# SparkFun_GPS_ZED-F9K.net
KiCad netlist of a schematic drawn in EAGLE
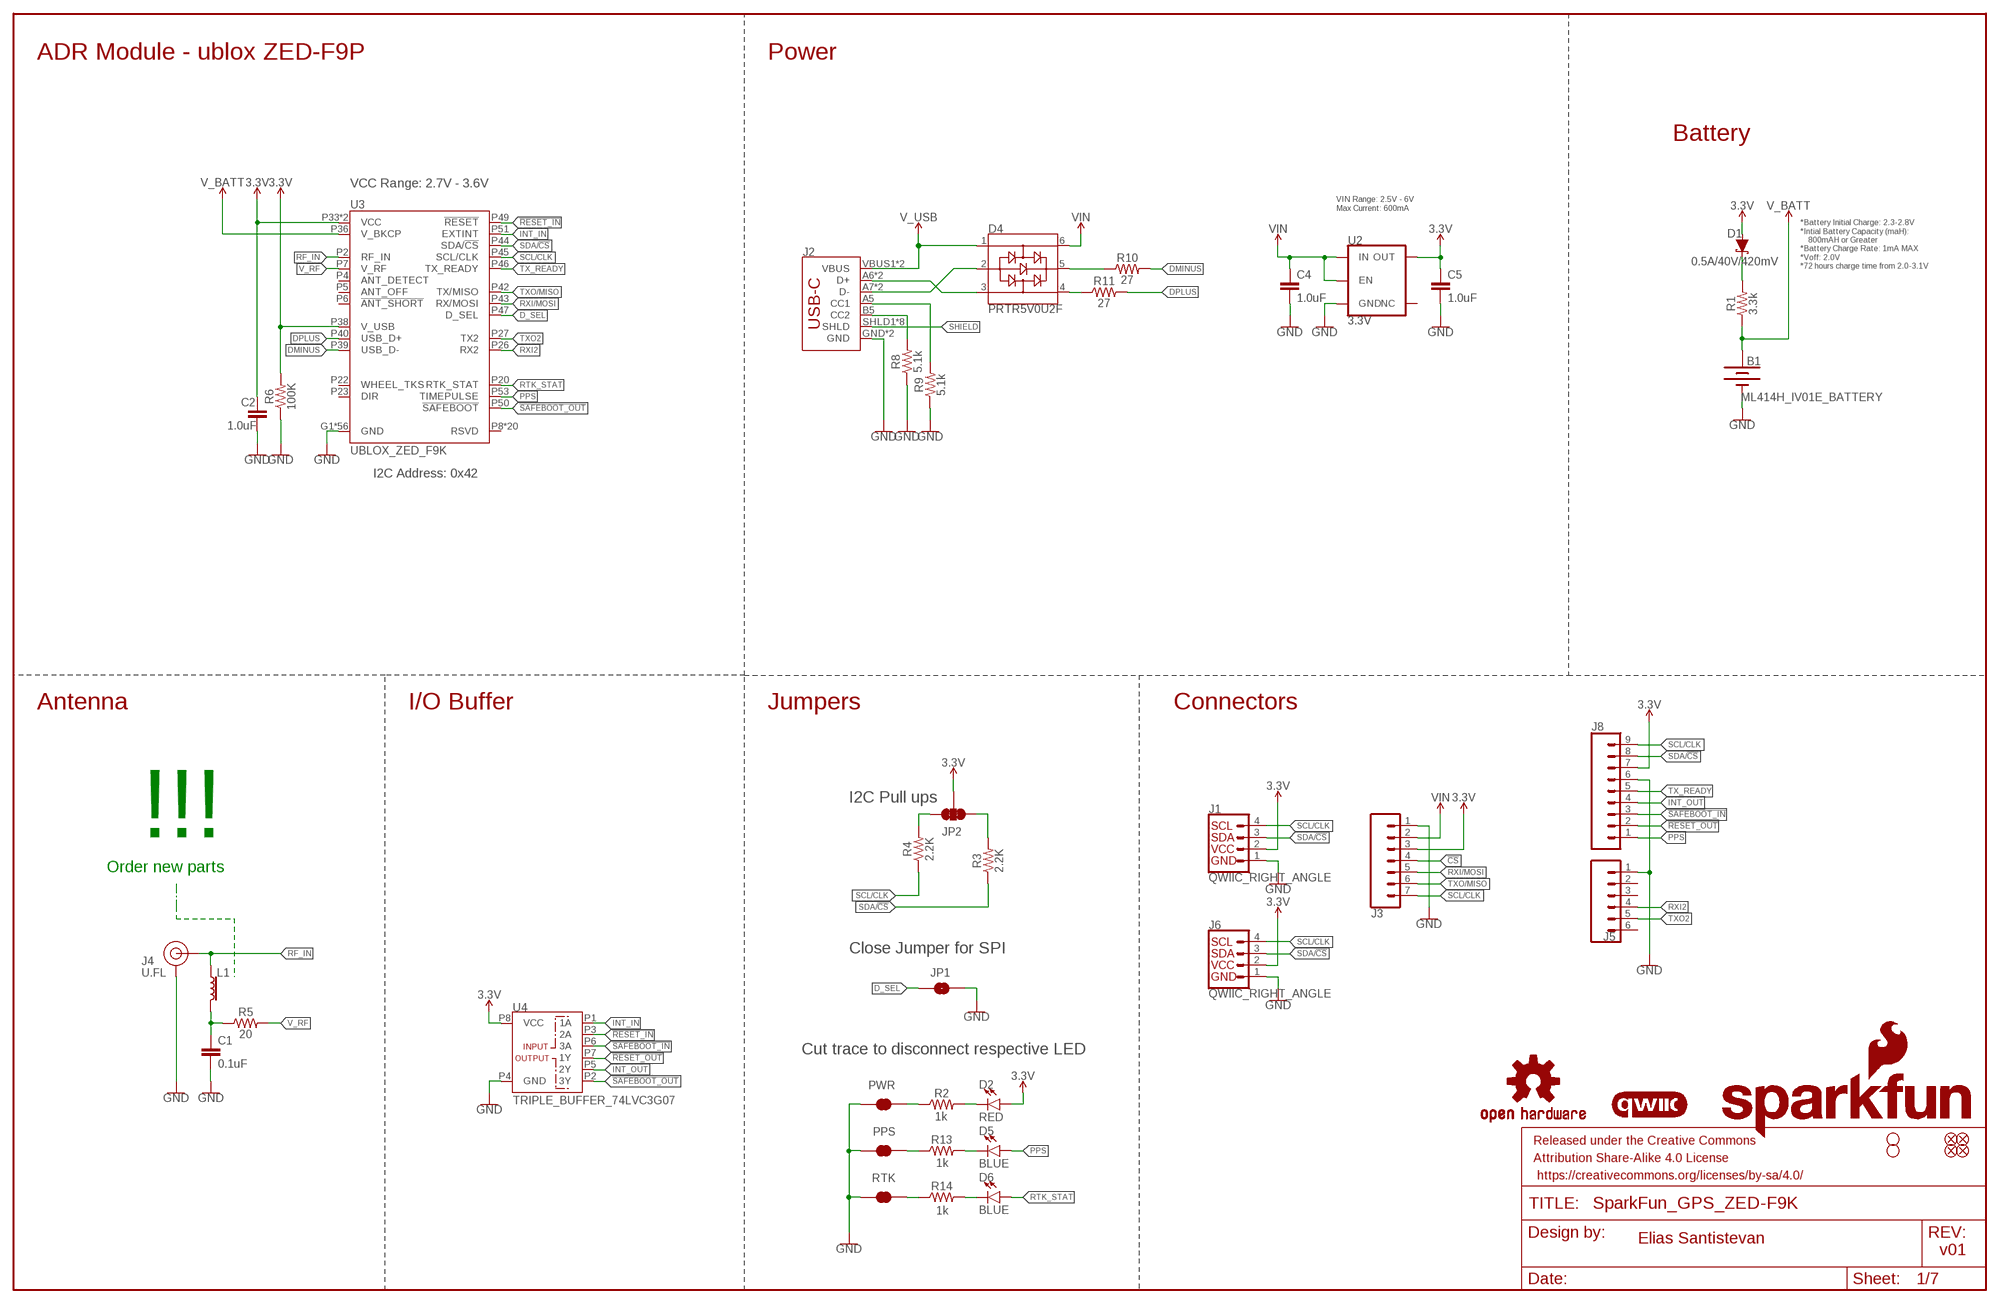
[diagram p0: schematic, sheet 1]

(export (version "E")
  (design (tool "Eeschema 10.0.6"))
  (components
    (comp (ref "B1")
      (value "ML414H_IV01E_BATTERY")
      (footprint "eagle-import:ML414H_IV01E")
      (libsource (lib "eagle-import") (part "ML414H_IV01E_BATTERY"))
    )
    (comp (ref "C1")
      (value "0.1uF")
      (footprint "eagle-import:0402")
      (libsource (lib "eagle-import") (part "0.1UF-0402-16V-10%"))
    )
    (comp (ref "C2")
      (value "1.0uF")
      (footprint "eagle-import:0402")
      (libsource (lib "eagle-import") (part "1.0UF-0402-16V-10%"))
    )
    (comp (ref "C4")
      (value "1.0uF")
      (footprint "eagle-import:0603")
      (libsource (lib "eagle-import") (part "1.0UF-0603-16V-10%-X7R"))
    )
    (comp (ref "C5")
      (value "1.0uF")
      (footprint "eagle-import:0603")
      (libsource (lib "eagle-import") (part "1.0UF-0603-16V-10%-X7R"))
    )
    (comp (ref "D1")
      (value "0.5A/40V/420mV")
      (footprint "eagle-import:SOD-323")
      (libsource (lib "eagle-import") (part "DIODE-SCHOTTKY-PMEG4005EJ"))
    )
    (comp (ref "D2")
      (value "RED")
      (footprint "eagle-import:LED-0603")
      (libsource (lib "eagle-import") (part "LED-RED0603"))
    )
    (comp (ref "D4")
      (value "PRTR5V0U2F")
      (footprint "eagle-import:SOT886")
      (libsource (lib "eagle-import") (part "PRTR5V0U2F"))
    )
    (comp (ref "D5")
      (value "BLUE")
      (footprint "eagle-import:LED-0603")
      (libsource (lib "eagle-import") (part "LED-BLUE0603"))
    )
    (comp (ref "D6")
      (value "BLUE")
      (footprint "eagle-import:LED-0603")
      (libsource (lib "eagle-import") (part "LED-BLUE0603"))
    )
    (comp (ref "FD1")
      (value "FIDUCIALUFIDUCIAL")
      (footprint "eagle-import:FIDUCIAL-MICRO")
      (libsource (lib "eagle-import") (part "FIDUCIALUFIDUCIAL"))
    )
    (comp (ref "FD2")
      (value "FIDUCIALUFIDUCIAL")
      (footprint "eagle-import:FIDUCIAL-MICRO")
      (libsource (lib "eagle-import") (part "FIDUCIALUFIDUCIAL"))
    )
    (comp (ref "FD3")
      (value "FIDUCIALUFIDUCIAL")
      (footprint "eagle-import:FIDUCIAL-MICRO")
      (libsource (lib "eagle-import") (part "FIDUCIALUFIDUCIAL"))
    )
    (comp (ref "FD4")
      (value "FIDUCIALUFIDUCIAL")
      (footprint "eagle-import:FIDUCIAL-MICRO")
      (libsource (lib "eagle-import") (part "FIDUCIALUFIDUCIAL"))
    )
    (comp (ref "FRAME2")
      (value "FRAME-LEDGER")
      (footprint "eagle-import:CREATIVE_COMMONS")
      (libsource (lib "eagle-import") (part "FRAME-LEDGER"))
    )
    (comp (ref "H2")
      (value "STAND-OFFTIGHT")
      (footprint "eagle-import:STAND-OFF-TIGHT")
      (libsource (lib "eagle-import") (part "STAND-OFFTIGHT"))
    )
    (comp (ref "H3")
      (value "STAND-OFFTIGHT")
      (footprint "eagle-import:STAND-OFF-TIGHT")
      (libsource (lib "eagle-import") (part "STAND-OFFTIGHT"))
    )
    (comp (ref "J1")
      (value "QWIIC_RIGHT_ANGLE")
      (footprint "eagle-import:JST04_1MM_RA")
      (libsource (lib "eagle-import") (part "QWIIC_CONNECTORJS-1MM"))
    )
    (comp (ref "J2")
      (value "USB_C2-LAYER")
      (footprint "eagle-import:USB-C-16P")
      (libsource (lib "eagle-import") (part "USB_C2-LAYER"))
    )
    (comp (ref "J3")
      (value "CONN_07NO_SILK")
      (footprint "eagle-import:1X07_NO_SILK")
      (libsource (lib "eagle-import") (part "CONN_07NO_SILK"))
    )
    (comp (ref "J4")
      (value "U.FL")
      (footprint "eagle-import:U.FL")
      (libsource (lib "eagle-import") (part "U.FL2PIN"))
    )
    (comp (ref "J5")
      (value "CONN_06NO_SILK_NO_POP")
      (footprint "eagle-import:1X06_NO_SILK")
      (libsource (lib "eagle-import") (part "CONN_06NO_SILK_NO_POP"))
    )
    (comp (ref "J6")
      (value "QWIIC_RIGHT_ANGLE")
      (footprint "eagle-import:JST04_1MM_RA")
      (libsource (lib "eagle-import") (part "QWIIC_CONNECTORJS-1MM"))
    )
    (comp (ref "J8")
      (value "CONN_09NO_SILK")
      (footprint "eagle-import:1X09_NO_SILK")
      (libsource (lib "eagle-import") (part "CONN_09NO_SILK"))
    )
    (comp (ref "JP1")
      (value "JUMPER-SMT_2_NO_SILK")
      (footprint "eagle-import:SMT-JUMPER_2_NO_SILK")
      (libsource (lib "eagle-import") (part "JUMPER-SMT_2_NO_SILK"))
    )
    (comp (ref "JP2")
      (value "JUMPER-SMT_3_2-NC_TRACE_SILK")
      (footprint "eagle-import:SMT-JUMPER_3_2-NC_TRACE_SILK")
      (libsource (lib "eagle-import") (part "JUMPER-SMT_3_2-NC_TRACE_SILK"))
    )
    (comp (ref "L1")
      (value "3.9NH")
      (footprint "eagle-import:0402")
      (fields (field (name "MFG_PART") "BLM15HB121SN1D"))
      (libsource (lib "eagle-import") (part "FERRITE_BEAD-120_OHM-0402"))
    )
    (comp (ref "LOGO1")
      (value "SFE_LOGO_NAME_FLAME.2_INCH")
      (footprint "eagle-import:SFE_LOGO_NAME_FLAME_.2")
      (libsource (lib "eagle-import") (part "SFE_LOGO_NAME_FLAME.2_INCH"))
    )
    (comp (ref "LOGO2")
      (value "QWIIC_LOGO_4MM")
      (footprint "eagle-import:QWIIC_4MM")
      (libsource (lib "eagle-import") (part "QWIIC_LOGO_4MM"))
    )
    (comp (ref "LOGO3")
      (value "OSHW-LOGOM")
      (footprint "eagle-import:OSHW-LOGO-M")
      (libsource (lib "eagle-import") (part "OSHW-LOGOM"))
    )
    (comp (ref "PPS")
      (value "JUMPER-SMT_2_NC_TRACE_SILK")
      (footprint "eagle-import:SMT-JUMPER_2_NC_TRACE_SILK")
      (libsource (lib "eagle-import") (part "JUMPER-SMT_2_NC_TRACE_SILK"))
    )
    (comp (ref "PWR")
      (value "JUMPER-SMT_2_NC_TRACE_SILK")
      (footprint "eagle-import:SMT-JUMPER_2_NC_TRACE_SILK")
      (libsource (lib "eagle-import") (part "JUMPER-SMT_2_NC_TRACE_SILK"))
    )
    (comp (ref "R1")
      (value "3.3k")
      (footprint "eagle-import:0603")
      (libsource (lib "eagle-import") (part "3.3KOHM-0603-1/10W-1%"))
    )
    (comp (ref "R2")
      (value "1KOHM-0402-1/16W-1%")
      (footprint "eagle-import:0402")
      (libsource (lib "eagle-import") (part "1KOHM-0402-1/16W-1%"))
    )
    (comp (ref "R3")
      (value "2.2K")
      (footprint "eagle-import:0402")
      (libsource (lib "eagle-import") (part "2.2KOHM-0402-1/16W-1%"))
    )
    (comp (ref "R4")
      (value "2.2K")
      (footprint "eagle-import:0402")
      (libsource (lib "eagle-import") (part "2.2KOHM-0402-1/16W-1%"))
    )
    (comp (ref "R5")
      (value "20")
      (footprint "eagle-import:0603")
      (libsource (lib "eagle-import") (part "20OHM-0603-1/10W-1%"))
    )
    (comp (ref "R6")
      (value "100K")
      (footprint "eagle-import:0402")
      (libsource (lib "eagle-import") (part "100KOHM-0402-1/16W-1%"))
    )
    (comp (ref "R8")
      (value "5.1k")
      (footprint "eagle-import:0402")
      (libsource (lib "eagle-import") (part "5.1KOHM-0402-1/16W-1%"))
    )
    (comp (ref "R9")
      (value "5.1k")
      (footprint "eagle-import:0402")
      (libsource (lib "eagle-import") (part "5.1KOHM-0402-1/16W-1%"))
    )
    (comp (ref "R10")
      (value "27")
      (footprint "eagle-import:0603")
      (libsource (lib "eagle-import") (part "27OHM-0603-1/10W-1%"))
    )
    (comp (ref "R11")
      (value "27")
      (footprint "eagle-import:0603")
      (libsource (lib "eagle-import") (part "27OHM-0603-1/10W-1%"))
    )
    (comp (ref "R13")
      (value "1KOHM-0402-1/16W-1%")
      (footprint "eagle-import:0402")
      (libsource (lib "eagle-import") (part "1KOHM-0402-1/16W-1%"))
    )
    (comp (ref "R14")
      (value "1KOHM-0402-1/16W-1%")
      (footprint "eagle-import:0402")
      (libsource (lib "eagle-import") (part "1KOHM-0402-1/16W-1%"))
    )
    (comp (ref "RTK")
      (value "JUMPER-SMT_2_NC_TRACE_SILK")
      (footprint "eagle-import:SMT-JUMPER_2_NC_TRACE_SILK")
      (libsource (lib "eagle-import") (part "JUMPER-SMT_2_NC_TRACE_SILK"))
    )
    (comp (ref "U2")
      (value "3.3V")
      (footprint "eagle-import:SOT23-5")
      (libsource (lib "eagle-import") (part "V_REG_AP2112K-3.3V"))
    )
    (comp (ref "U3")
      (value "UBLOX_ZED_F9K")
      (footprint "eagle-import:UBLOX_ZED_F9K")
      (libsource (lib "eagle-import") (part "UBLOX_ZED_F9K"))
    )
    (comp (ref "U4")
      (value "TRIPLE_BUFFER_74LVC3G07")
      (footprint "eagle-import:SOP_8-PIN")
      (libsource (lib "eagle-import") (part "TRIPLE_BUFFER_74LVC3G07"))
    )
  )
  (nets
    (net (code "1") (name "3.3V") (class "Default")
      (node (ref "C2") (pin "1") (pinfunction "1_1") (pintype "passive"))
      (node (ref "C5") (pin "1") (pinfunction "1_1") (pintype "passive"))
      (node (ref "D1") (pin "A") (pinfunction "A_A") (pintype "passive"))
      (node (ref "D2") (pin "A") (pinfunction "A_A") (pintype "passive"))
      (node (ref "J1") (pin "2") (pinfunction "2_2") (pintype "power_in"))
      (node (ref "J3") (pin "3") (pinfunction "3_3") (pintype "passive"))
      (node (ref "J6") (pin "2") (pinfunction "2_2") (pintype "power_in"))
      (node (ref "J8") (pin "7") (pinfunction "7_7") (pintype "passive"))
      (node (ref "JP2") (pin "2") (pinfunction "2_2") (pintype "passive"))
      (node (ref "R6") (pin "2") (pinfunction "2_2") (pintype "passive"))
      (node (ref "U2") (pin "5") (pinfunction "OUT_5") (pintype "passive"))
      (node (ref "U3") (pin "P33") (pinfunction "VCC_P33") (pintype "power_in"))
      (node (ref "U3") (pin "P34") (pinfunction "VCC_P34") (pintype "power_in"))
      (node (ref "U3") (pin "P38") (pinfunction "V_USB_P38") (pintype "power_in"))
      (node (ref "U4") (pin "P8") (pinfunction "VCC_P8") (pintype "power_in"))
    )
    (net (code "2") (name "DMINUS") (class "Default")
      (node (ref "R10") (pin "2") (pinfunction "2_2") (pintype "passive"))
      (node (ref "U3") (pin "P39") (pinfunction "USB_D-_P39") (pintype "bidirectional"))
    )
    (net (code "3") (name "DPLUS") (class "Default")
      (node (ref "R11") (pin "2") (pinfunction "2_2") (pintype "passive"))
      (node (ref "U3") (pin "P40") (pinfunction "USB_D+_P40") (pintype "bidirectional"))
    )
    (net (code "4") (name "D_SEL") (class "Default")
      (node (ref "JP1") (pin "1") (pinfunction "1_1") (pintype "passive"))
      (node (ref "U3") (pin "P47") (pinfunction "D_SEL_P47") (pintype "bidirectional"))
    )
    (net (code "5") (name "GND") (class "Default")
      (node (ref "B1") (pin "-") (pinfunction "-_-") (pintype "power_in"))
      (node (ref "C1") (pin "2") (pinfunction "2_2") (pintype "passive"))
      (node (ref "C2") (pin "2") (pinfunction "2_2") (pintype "passive"))
      (node (ref "C4") (pin "2") (pinfunction "2_2") (pintype "passive"))
      (node (ref "C5") (pin "2") (pinfunction "2_2") (pintype "passive"))
      (node (ref "J1") (pin "1") (pinfunction "1_1") (pintype "power_in"))
      (node (ref "J2") (pin "GND") (pinfunction "GND_GND") (pintype "bidirectional"))
      (node (ref "J2") (pin "GND2") (pinfunction "GND_GND2") (pintype "bidirectional"))
      (node (ref "J3") (pin "1") (pinfunction "1_1") (pintype "passive"))
      (node (ref "J4") (pin "1") (pinfunction "GND_1") (pintype "bidirectional"))
      (node (ref "J4") (pin "2") (pinfunction "GND_2") (pintype "bidirectional"))
      (node (ref "J5") (pin "1") (pinfunction "1_1") (pintype "passive"))
      (node (ref "J6") (pin "1") (pinfunction "1_1") (pintype "power_in"))
      (node (ref "J8") (pin "6") (pinfunction "6_6") (pintype "passive"))
      (node (ref "JP1") (pin "2") (pinfunction "2_2") (pintype "passive"))
      (node (ref "PPS") (pin "1") (pinfunction "1_1") (pintype "passive"))
      (node (ref "PWR") (pin "1") (pinfunction "1_1") (pintype "passive"))
      (node (ref "R6") (pin "1") (pinfunction "1_1") (pintype "passive"))
      (node (ref "R8") (pin "1") (pinfunction "1_1") (pintype "passive"))
      (node (ref "R9") (pin "1") (pinfunction "1_1") (pintype "passive"))
      (node (ref "RTK") (pin "1") (pinfunction "1_1") (pintype "passive"))
      (node (ref "U2") (pin "2") (pinfunction "GND_2") (pintype "input"))
      (node (ref "U3") (pin "G1") (pinfunction "GND_G1") (pintype "power_in"))
      (node (ref "U3") (pin "G10") (pinfunction "GND_G10") (pintype "power_in"))
      (node (ref "U3") (pin "G11") (pinfunction "GND_G11") (pintype "power_in"))
      (node (ref "U3") (pin "G12") (pinfunction "GND_G12") (pintype "power_in"))
      (node (ref "U3") (pin "G13") (pinfunction "GND_G13") (pintype "power_in"))
      (node (ref "U3") (pin "G14") (pinfunction "GND_G14") (pintype "power_in"))
      (node (ref "U3") (pin "G15") (pinfunction "GND_G15") (pintype "power_in"))
      (node (ref "U3") (pin "G16") (pinfunction "GND_G16") (pintype "power_in"))
      (node (ref "U3") (pin "G17") (pinfunction "GND_G17") (pintype "power_in"))
      (node (ref "U3") (pin "G18") (pinfunction "GND_G18") (pintype "power_in"))
      (node (ref "U3") (pin "G19") (pinfunction "GND_G19") (pintype "power_in"))
      (node (ref "U3") (pin "G2") (pinfunction "GND_G2") (pintype "power_in"))
      (node (ref "U3") (pin "G20") (pinfunction "GND_G20") (pintype "power_in"))
      (node (ref "U3") (pin "G21") (pinfunction "GND_G21") (pintype "power_in"))
      (node (ref "U3") (pin "G22") (pinfunction "GND_G22") (pintype "power_in"))
      (node (ref "U3") (pin "G23") (pinfunction "GND_G23") (pintype "power_in"))
      (node (ref "U3") (pin "G24") (pinfunction "GND_G24") (pintype "power_in"))
      (node (ref "U3") (pin "G25") (pinfunction "GND_G25") (pintype "power_in"))
      (node (ref "U3") (pin "G26") (pinfunction "GND_G26") (pintype "power_in"))
      (node (ref "U3") (pin "G27") (pinfunction "GND_G27") (pintype "power_in"))
      (node (ref "U3") (pin "G28") (pinfunction "GND_G28") (pintype "power_in"))
      (node (ref "U3") (pin "G29") (pinfunction "GND_G29") (pintype "power_in"))
      (node (ref "U3") (pin "G3") (pinfunction "GND_G3") (pintype "power_in"))
      (node (ref "U3") (pin "G30") (pinfunction "GND_G30") (pintype "power_in"))
      (node (ref "U3") (pin "G31") (pinfunction "GND_G31") (pintype "power_in"))
      (node (ref "U3") (pin "G32") (pinfunction "GND_G32") (pintype "power_in"))
      (node (ref "U3") (pin "G33") (pinfunction "GND_G33") (pintype "power_in"))
      (node (ref "U3") (pin "G34") (pinfunction "GND_G34") (pintype "power_in"))
      (node (ref "U3") (pin "G35") (pinfunction "GND_G35") (pintype "power_in"))
      (node (ref "U3") (pin "G36") (pinfunction "GND_G36") (pintype "power_in"))
      (node (ref "U3") (pin "G37") (pinfunction "GND_G37") (pintype "power_in"))
      (node (ref "U3") (pin "G38") (pinfunction "GND_G38") (pintype "power_in"))
      (node (ref "U3") (pin "G39") (pinfunction "GND_G39") (pintype "power_in"))
      (node (ref "U3") (pin "G4") (pinfunction "GND_G4") (pintype "power_in"))
      (node (ref "U3") (pin "G40") (pinfunction "GND_G40") (pintype "power_in"))
      (node (ref "U3") (pin "G41") (pinfunction "GND_G41") (pintype "power_in"))
      (node (ref "U3") (pin "G42") (pinfunction "GND_G42") (pintype "power_in"))
      (node (ref "U3") (pin "G43") (pinfunction "GND_G43") (pintype "power_in"))
      (node (ref "U3") (pin "G44") (pinfunction "GND_G44") (pintype "power_in"))
      (node (ref "U3") (pin "G45") (pinfunction "GND_G45") (pintype "power_in"))
      (node (ref "U3") (pin "G46") (pinfunction "GND_G46") (pintype "power_in"))
      (node (ref "U3") (pin "G47") (pinfunction "GND_G47") (pintype "power_in"))
      (node (ref "U3") (pin "G48") (pinfunction "GND_G48") (pintype "power_in"))
      (node (ref "U3") (pin "G5") (pinfunction "GND_G5") (pintype "power_in"))
      (node (ref "U3") (pin "G6") (pinfunction "GND_G6") (pintype "power_in"))
      (node (ref "U3") (pin "G7") (pinfunction "GND_G7") (pintype "power_in"))
      (node (ref "U3") (pin "G8") (pinfunction "GND_G8") (pintype "power_in"))
      (node (ref "U3") (pin "G9") (pinfunction "GND_G9") (pintype "power_in"))
      (node (ref "U3") (pin "P1") (pinfunction "GND_P1") (pintype "power_in"))
      (node (ref "U3") (pin "P12") (pinfunction "GND_P12") (pintype "power_in"))
      (node (ref "U3") (pin "P14") (pinfunction "GND_P14") (pintype "power_in"))
      (node (ref "U3") (pin "P3") (pinfunction "GND_P3") (pintype "power_in"))
      (node (ref "U3") (pin "P32") (pinfunction "GND_P32") (pintype "power_in"))
      (node (ref "U3") (pin "P37") (pinfunction "GND_P37") (pintype "power_in"))
      (node (ref "U3") (pin "P41") (pinfunction "GND_P41") (pintype "power_in"))
      (node (ref "U3") (pin "P48") (pinfunction "GND_P48") (pintype "power_in"))
      (node (ref "U4") (pin "P4") (pinfunction "GND_P4") (pintype "power_in"))
    )
    (net (code "6") (name "INT_IN") (class "Default")
      (node (ref "U3") (pin "P51") (pinfunction "EXTINT_P51") (pintype "bidirectional"))
      (node (ref "U4") (pin "P1") (pinfunction "1A_P1") (pintype "bidirectional"))
    )
    (net (code "7") (name "INT_OUT") (class "Default")
      (node (ref "J8") (pin "4") (pinfunction "4_4") (pintype "passive"))
      (node (ref "U4") (pin "P5") (pinfunction "2Y_P5") (pintype "bidirectional"))
    )
    (net (code "8") (name "Net-(C1-Pad1)") (class "Default")
      (node (ref "C1") (pin "1") (pinfunction "1_1") (pintype "passive"))
      (node (ref "L1") (pin "2") (pinfunction "2_2") (pintype "passive"))
      (node (ref "R5") (pin "1") (pinfunction "1_1") (pintype "passive"))
    )
    (net (code "9") (name "Net-(D1-PadC)") (class "Default")
      (node (ref "D1") (pin "C") (pinfunction "C_C") (pintype "passive"))
      (node (ref "R1") (pin "2") (pinfunction "2_2") (pintype "passive"))
    )
    (net (code "10") (name "Net-(D2-PadC)") (class "Default")
      (node (ref "D2") (pin "C") (pinfunction "C_C") (pintype "passive"))
      (node (ref "R2") (pin "2") (pinfunction "2_2") (pintype "passive"))
    )
    (net (code "11") (name "Net-(D4-Pad2)") (class "Default")
      (node (ref "D4") (pin "2") (pinfunction "2_2") (pintype "bidirectional"))
      (node (ref "J2") (pin "A7") (pinfunction "D-_A7") (pintype "bidirectional"))
      (node (ref "J2") (pin "B7") (pinfunction "D-_B7") (pintype "bidirectional"))
    )
    (net (code "12") (name "Net-(D4-Pad3)") (class "Default")
      (node (ref "D4") (pin "3") (pinfunction "3_3") (pintype "bidirectional"))
      (node (ref "J2") (pin "A6") (pinfunction "D+_A6") (pintype "bidirectional"))
      (node (ref "J2") (pin "B6") (pinfunction "D+_B6") (pintype "bidirectional"))
    )
    (net (code "13") (name "Net-(D4-Pad4)") (class "Default")
      (node (ref "D4") (pin "4") (pinfunction "4_4") (pintype "bidirectional"))
      (node (ref "R11") (pin "1") (pinfunction "1_1") (pintype "passive"))
    )
    (net (code "14") (name "Net-(D4-Pad5)") (class "Default")
      (node (ref "D4") (pin "5") (pinfunction "5_5") (pintype "bidirectional"))
      (node (ref "R10") (pin "1") (pinfunction "1_1") (pintype "passive"))
    )
    (net (code "15") (name "Net-(D5-PadC)") (class "Default")
      (node (ref "D5") (pin "C") (pinfunction "C_C") (pintype "passive"))
      (node (ref "R13") (pin "2") (pinfunction "2_2") (pintype "passive"))
    )
    (net (code "16") (name "Net-(D6-PadC)") (class "Default")
      (node (ref "D6") (pin "C") (pinfunction "C_C") (pintype "passive"))
      (node (ref "R14") (pin "2") (pinfunction "2_2") (pintype "passive"))
    )
    (net (code "17") (name "Net-(J2-CC1)") (class "Default")
      (node (ref "J2") (pin "A5") (pinfunction "CC1_A5") (pintype "bidirectional"))
      (node (ref "R9") (pin "2") (pinfunction "2_2") (pintype "passive"))
    )
    (net (code "18") (name "Net-(J2-CC2)") (class "Default")
      (node (ref "J2") (pin "B5") (pinfunction "CC2_B5") (pintype "bidirectional"))
      (node (ref "R8") (pin "2") (pinfunction "2_2") (pintype "passive"))
    )
    (net (code "19") (name "Net-(JP2-Pad1)") (class "Default")
      (node (ref "JP2") (pin "1") (pinfunction "1_1") (pintype "passive"))
      (node (ref "R3") (pin "2") (pinfunction "2_2") (pintype "passive"))
    )
    (net (code "20") (name "Net-(JP2-Pad3)") (class "Default")
      (node (ref "JP2") (pin "3") (pinfunction "3_3") (pintype "passive"))
      (node (ref "R4") (pin "2") (pinfunction "2_2") (pintype "passive"))
    )
    (net (code "21") (name "Net-(PPS-Pad2)") (class "Default")
      (node (ref "PPS") (pin "2") (pinfunction "2_2") (pintype "passive"))
      (node (ref "R13") (pin "1") (pinfunction "1_1") (pintype "passive"))
    )
    (net (code "22") (name "Net-(PWR-Pad2)") (class "Default")
      (node (ref "PWR") (pin "2") (pinfunction "2_2") (pintype "passive"))
      (node (ref "R2") (pin "1") (pinfunction "1_1") (pintype "passive"))
    )
    (net (code "23") (name "Net-(R14-Pad1)") (class "Default")
      (node (ref "R14") (pin "1") (pinfunction "1_1") (pintype "passive"))
      (node (ref "RTK") (pin "2") (pinfunction "2_2") (pintype "passive"))
    )
    (net (code "24") (name "PPS") (class "Default")
      (node (ref "D5") (pin "A") (pinfunction "A_A") (pintype "passive"))
      (node (ref "J8") (pin "1") (pinfunction "1_1") (pintype "passive"))
      (node (ref "U3") (pin "P53") (pinfunction "TIMEPULSE_P53") (pintype "output"))
    )
    (net (code "25") (name "RF_IN") (class "Default")
      (node (ref "J4") (pin "FEED") (pinfunction "SIGNAL_FEED") (pintype "bidirectional"))
      (node (ref "L1") (pin "1") (pinfunction "1_1") (pintype "passive"))
      (node (ref "U3") (pin "P2") (pinfunction "RF_IN_P2") (pintype "input"))
    )
    (net (code "26") (name "RTK_STAT") (class "Default")
      (node (ref "D6") (pin "A") (pinfunction "A_A") (pintype "passive"))
      (node (ref "U3") (pin "P20") (pinfunction "RTK_STAT_P20") (pintype "output"))
    )
    (net (code "27") (name "RXI2") (class "Default")
      (node (ref "J5") (pin "4") (pinfunction "4_4") (pintype "passive"))
      (node (ref "U3") (pin "P26") (pinfunction "RX2_P26") (pintype "input"))
    )
    (net (code "28") (name "RXI{slash}MOSI") (class "Default")
      (node (ref "J3") (pin "5") (pinfunction "5_5") (pintype "passive"))
      (node (ref "U3") (pin "P43") (pinfunction "RX/MOSI_P43") (pintype "bidirectional"))
    )
    (net (code "29") (name "SCL{slash}CLK") (class "Default")
      (node (ref "J1") (pin "4") (pinfunction "4_4") (pintype "passive"))
      (node (ref "J3") (pin "7") (pinfunction "7_7") (pintype "passive"))
      (node (ref "J6") (pin "4") (pinfunction "4_4") (pintype "passive"))
      (node (ref "J8") (pin "9") (pinfunction "9_9") (pintype "passive"))
      (node (ref "R4") (pin "1") (pinfunction "1_1") (pintype "passive"))
      (node (ref "U3") (pin "P45") (pinfunction "SCL/CLK_P45") (pintype "bidirectional"))
    )
    (net (code "30") (name "SDA{slash}~{CS}") (class "Default")
      (node (ref "J1") (pin "3") (pinfunction "3_3") (pintype "passive"))
      (node (ref "J6") (pin "3") (pinfunction "3_3") (pintype "passive"))
      (node (ref "J8") (pin "8") (pinfunction "8_8") (pintype "passive"))
      (node (ref "R3") (pin "1") (pinfunction "1_1") (pintype "passive"))
      (node (ref "U3") (pin "P44") (pinfunction "SDA/~{CS}_P44") (pintype "bidirectional"))
    )
    (net (code "31") (name "SHIELD") (class "Default")
      (node (ref "J2") (pin "SHLD1") (pinfunction "SHLD_SHLD1") (pintype "bidirectional"))
      (node (ref "J2") (pin "SHLD2") (pinfunction "SHLD_SHLD2") (pintype "bidirectional"))
      (node (ref "J2") (pin "SHLD3") (pinfunction "SHLD_SHLD3") (pintype "bidirectional"))
      (node (ref "J2") (pin "SHLD4") (pinfunction "SHLD_SHLD4") (pintype "bidirectional"))
      (node (ref "J2") (pin "SHLD5") (pinfunction "SHLD_SHLD5") (pintype "bidirectional"))
      (node (ref "J2") (pin "SHLD6") (pinfunction "SHLD_SHLD6") (pintype "bidirectional"))
      (node (ref "J2") (pin "SHLD7") (pinfunction "SHLD_SHLD7") (pintype "bidirectional"))
      (node (ref "J2") (pin "SHLD8") (pinfunction "SHLD_SHLD8") (pintype "bidirectional"))
    )
    (net (code "32") (name "TXO2") (class "Default")
      (node (ref "J5") (pin "5") (pinfunction "5_5") (pintype "passive"))
      (node (ref "U3") (pin "P27") (pinfunction "TX2_P27") (pintype "output"))
    )
    (net (code "33") (name "TXO{slash}MISO") (class "Default")
      (node (ref "J3") (pin "6") (pinfunction "6_6") (pintype "passive"))
      (node (ref "U3") (pin "P42") (pinfunction "TX/MISO_P42") (pintype "bidirectional"))
    )
    (net (code "34") (name "TX_READY") (class "Default")
      (node (ref "J8") (pin "5") (pinfunction "5_5") (pintype "passive"))
      (node (ref "U3") (pin "P46") (pinfunction "TX_READY_P46") (pintype "bidirectional"))
    )
    (net (code "35") (name "VIN") (class "Default")
      (node (ref "C4") (pin "1") (pinfunction "1_1") (pintype "passive"))
      (node (ref "D4") (pin "6") (pinfunction "6_6") (pintype "bidirectional"))
      (node (ref "J3") (pin "2") (pinfunction "2_2") (pintype "passive"))
      (node (ref "U2") (pin "1") (pinfunction "IN_1") (pintype "input"))
      (node (ref "U2") (pin "3") (pinfunction "EN_3") (pintype "input"))
    )
    (net (code "36") (name "V_BATT") (class "Default")
      (node (ref "B1") (pin "+") (pinfunction "+_+") (pintype "power_in"))
      (node (ref "R1") (pin "1") (pinfunction "1_1") (pintype "passive"))
      (node (ref "U3") (pin "P36") (pinfunction "V_BKCP_P36") (pintype "power_in"))
    )
    (net (code "37") (name "V_RF") (class "Default")
      (node (ref "R5") (pin "2") (pinfunction "2_2") (pintype "passive"))
      (node (ref "U3") (pin "P7") (pinfunction "V_RF_P7") (pintype "output"))
    )
    (net (code "38") (name "V_USB") (class "Default")
      (node (ref "D4") (pin "1") (pinfunction "1_1") (pintype "bidirectional"))
      (node (ref "J2") (pin "VBUS1") (pinfunction "VBUS_VBUS1") (pintype "bidirectional"))
      (node (ref "J2") (pin "VBUS2") (pinfunction "VBUS_VBUS2") (pintype "bidirectional"))
    )
    (net (code "39") (name "unconnected-(J5-Pad2)") (class "Default")
      (node (ref "J5") (pin "2") (pinfunction "2_2") (pintype "passive"))
    )
    (net (code "40") (name "unconnected-(J5-Pad3)") (class "Default")
      (node (ref "J5") (pin "3") (pinfunction "3_3") (pintype "passive"))
    )
    (net (code "41") (name "unconnected-(J5-Pad6)") (class "Default")
      (node (ref "J5") (pin "6") (pinfunction "6_6") (pintype "passive"))
    )
    (net (code "42") (name "unconnected-(U2-NC-Pad4)") (class "Default")
      (node (ref "U2") (pin "4") (pinfunction "NC_4") (pintype "no_connect"))
    )
    (net (code "43") (name "unconnected-(U3-ANT_DETECT-PadP4)") (class "Default")
      (node (ref "U3") (pin "P4") (pinfunction "ANT_DETECT_P4") (pintype "input"))
    )
    (net (code "44") (name "unconnected-(U3-ANT_OFF-PadP5)") (class "Default")
      (node (ref "U3") (pin "P5") (pinfunction "ANT_OFF_P5") (pintype "output"))
    )
    (net (code "45") (name "unconnected-(U3-DIR-PadP23)") (class "Default")
      (node (ref "U3") (pin "P23") (pinfunction "DIR_P23") (pintype "input"))
    )
    (net (code "46") (name "unconnected-(U3-RSVD-PadP8)") (class "Default")
      (node (ref "U3") (pin "P8") (pinfunction "RSVD_P8") (pintype "no_connect"))
    )
    (net (code "47") (name "unconnected-(U3-RSVD-PadP9)") (class "Default")
      (node (ref "U3") (pin "P9") (pinfunction "RSVD_P9") (pintype "no_connect"))
    )
    (net (code "48") (name "unconnected-(U3-RSVD-PadP10)") (class "Default")
      (node (ref "U3") (pin "P10") (pinfunction "RSVD_P10") (pintype "no_connect"))
    )
    (net (code "49") (name "unconnected-(U3-RSVD-PadP11)") (class "Default")
      (node (ref "U3") (pin "P11") (pinfunction "RSVD_P11") (pintype "no_connect"))
    )
    (net (code "50") (name "unconnected-(U3-RSVD-PadP13)") (class "Default")
      (node (ref "U3") (pin "P13") (pinfunction "RSVD_P13") (pintype "no_connect"))
    )
    (net (code "51") (name "unconnected-(U3-RSVD-PadP15)") (class "Default")
      (node (ref "U3") (pin "P15") (pinfunction "RSVD_P15") (pintype "no_connect"))
    )
    (net (code "52") (name "unconnected-(U3-RSVD-PadP16)") (class "Default")
      (node (ref "U3") (pin "P16") (pinfunction "RSVD_P16") (pintype "no_connect"))
    )
    (net (code "53") (name "unconnected-(U3-RSVD-PadP17)") (class "Default")
      (node (ref "U3") (pin "P17") (pinfunction "RSVD_P17") (pintype "no_connect"))
    )
    (net (code "54") (name "unconnected-(U3-RSVD-PadP18)") (class "Default")
      (node (ref "U3") (pin "P18") (pinfunction "RSVD_P18") (pintype "no_connect"))
    )
    (net (code "55") (name "unconnected-(U3-RSVD-PadP19)") (class "Default")
      (node (ref "U3") (pin "P19") (pinfunction "RSVD_P19") (pintype "no_connect"))
    )
    (net (code "56") (name "unconnected-(U3-RSVD-PadP21)") (class "Default")
      (node (ref "U3") (pin "P21") (pinfunction "RSVD_P21") (pintype "no_connect"))
    )
    (net (code "57") (name "unconnected-(U3-RSVD-PadP24)") (class "Default")
      (node (ref "U3") (pin "P24") (pinfunction "RSVD_P24") (pintype "no_connect"))
    )
    (net (code "58") (name "unconnected-(U3-RSVD-PadP25)") (class "Default")
      (node (ref "U3") (pin "P25") (pinfunction "RSVD_P25") (pintype "no_connect"))
    )
    (net (code "59") (name "unconnected-(U3-RSVD-PadP28)") (class "Default")
      (node (ref "U3") (pin "P28") (pinfunction "RSVD_P28") (pintype "no_connect"))
    )
    (net (code "60") (name "unconnected-(U3-RSVD-PadP29)") (class "Default")
      (node (ref "U3") (pin "P29") (pinfunction "RSVD_P29") (pintype "no_connect"))
    )
    (net (code "61") (name "unconnected-(U3-RSVD-PadP30)") (class "Default")
      (node (ref "U3") (pin "P30") (pinfunction "RSVD_P30") (pintype "no_connect"))
    )
    (net (code "62") (name "unconnected-(U3-RSVD-PadP31)") (class "Default")
      (node (ref "U3") (pin "P31") (pinfunction "RSVD_P31") (pintype "no_connect"))
    )
    (net (code "63") (name "unconnected-(U3-RSVD-PadP35)") (class "Default")
      (node (ref "U3") (pin "P35") (pinfunction "RSVD_P35") (pintype "no_connect"))
    )
    (net (code "64") (name "unconnected-(U3-RSVD-PadP52)") (class "Default")
      (node (ref "U3") (pin "P52") (pinfunction "RSVD_P52") (pintype "no_connect"))
    )
    (net (code "65") (name "unconnected-(U3-RSVD-PadP54)") (class "Default")
      (node (ref "U3") (pin "P54") (pinfunction "RSVD_P54") (pintype "no_connect"))
    )
    (net (code "66") (name "unconnected-(U3-WHEEL_TKS-PadP22)") (class "Default")
      (node (ref "U3") (pin "P22") (pinfunction "WHEEL_TKS_P22") (pintype "input"))
    )
    (net (code "67") (name "unconnected-(U3-~{ANT_SHORT}-PadP6)") (class "Default")
      (node (ref "U3") (pin "P6") (pinfunction "~{ANT_SHORT}_P6") (pintype "output"))
    )
    (net (code "68") (name "~{CS}") (class "Default")
      (node (ref "J3") (pin "4") (pinfunction "4_4") (pintype "passive"))
    )
    (net (code "69") (name "~{RESET_IN}") (class "Default")
      (node (ref "U3") (pin "P49") (pinfunction "~{RESET}_P49") (pintype "bidirectional"))
      (node (ref "U4") (pin "P3") (pinfunction "2A_P3") (pintype "bidirectional"))
    )
    (net (code "70") (name "~{RESET_OUT}") (class "Default")
      (node (ref "J8") (pin "2") (pinfunction "2_2") (pintype "passive"))
      (node (ref "U4") (pin "P7") (pinfunction "1Y_P7") (pintype "bidirectional"))
    )
    (net (code "71") (name "~{SAFEBOOT_IN}") (class "Default")
      (node (ref "J8") (pin "3") (pinfunction "3_3") (pintype "passive"))
      (node (ref "U4") (pin "P6") (pinfunction "3A_P6") (pintype "bidirectional"))
    )
    (net (code "72") (name "~{SAFEBOOT_OUT}") (class "Default")
      (node (ref "U3") (pin "P50") (pinfunction "~{SAFEBOOT}_P50") (pintype "input"))
      (node (ref "U4") (pin "P2") (pinfunction "3Y_P2") (pintype "bidirectional"))
    )
  )
)
